# schemat.net
KiCad netlist of a schematic drawn in EAGLE
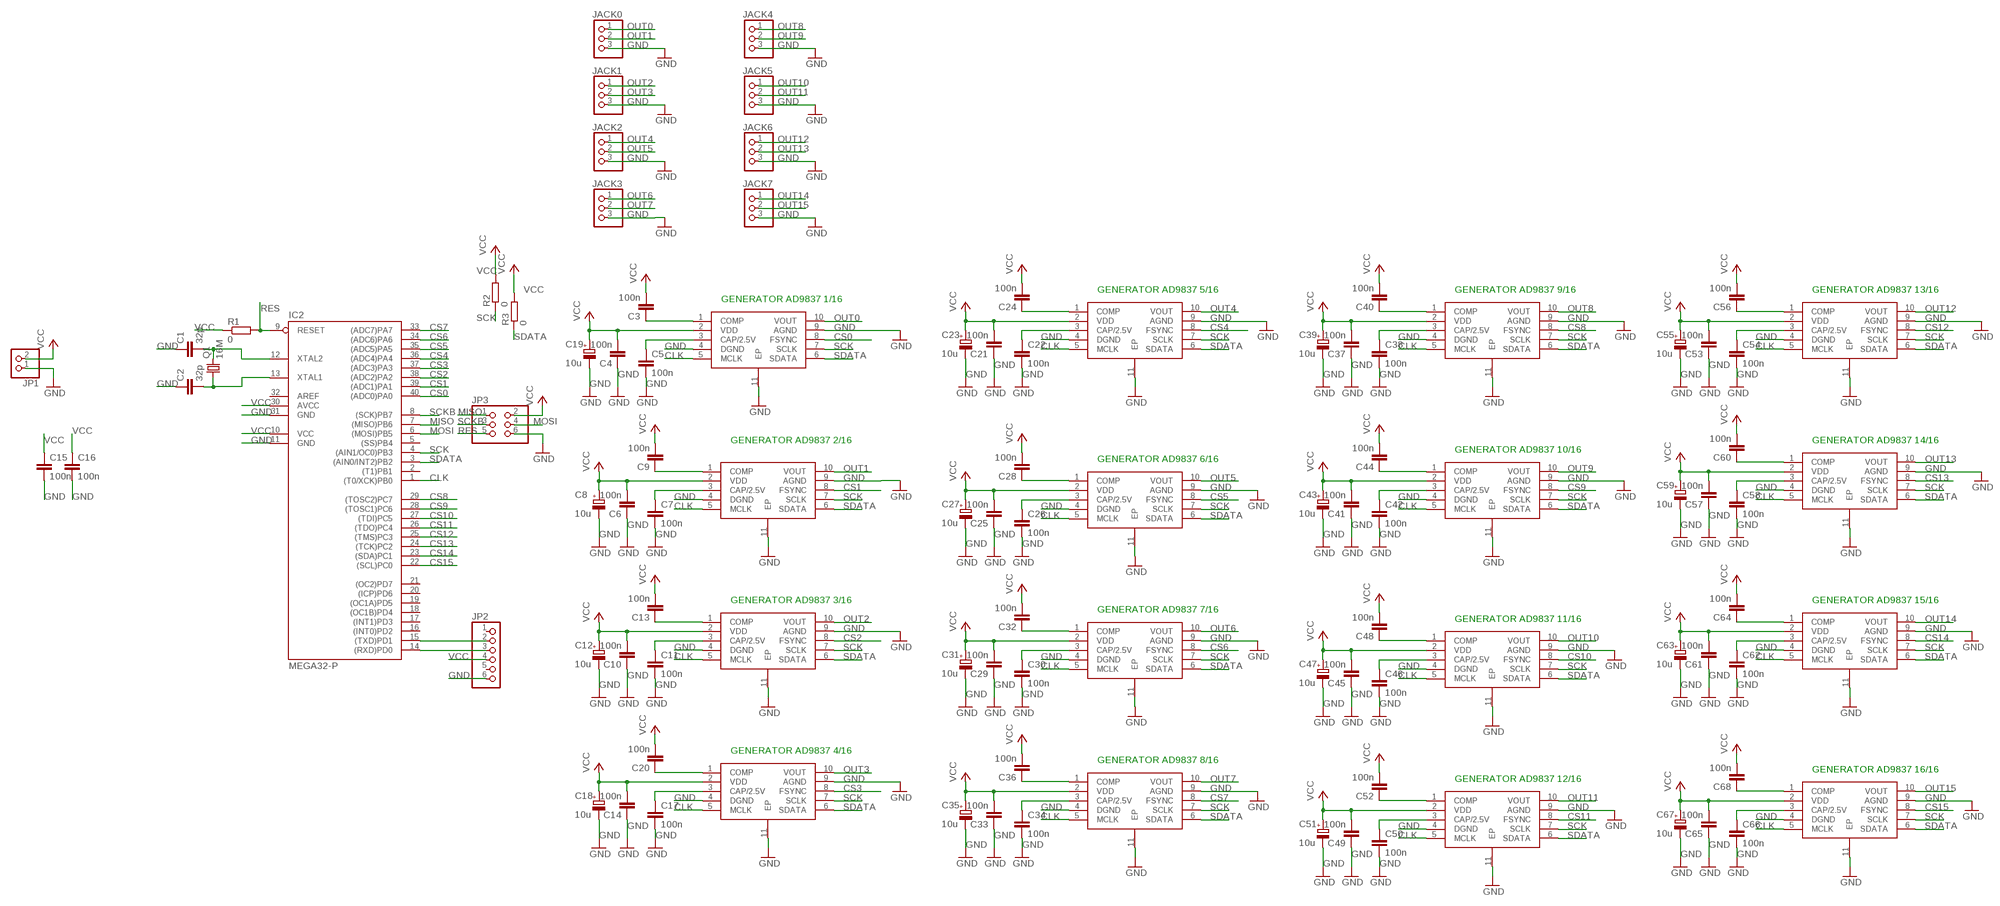
[diagram p0: schematic, sheet 1]

(export (version "E")
  (design (tool "Eeschema 10.0.6"))
  (components
    (comp (ref "C1")
      (value "32p")
      (footprint "eagle-import:C1206")
      (libsource (lib "eagle-import") (part "rcl_334_C-EUC1206"))
    )
    (comp (ref "C2")
      (value "32p")
      (footprint "eagle-import:C1206")
      (libsource (lib "eagle-import") (part "rcl_334_C-EUC1206"))
    )
    (comp (ref "C3")
      (value "100n")
      (footprint "eagle-import:C1206")
      (libsource (lib "eagle-import") (part "C-EUC1206"))
    )
    (comp (ref "C4")
      (value "100n")
      (footprint "eagle-import:C1206")
      (libsource (lib "eagle-import") (part "C-EUC1206"))
    )
    (comp (ref "C5")
      (value "100n")
      (footprint "eagle-import:C1206")
      (libsource (lib "eagle-import") (part "C-EUC1206"))
    )
    (comp (ref "C6")
      (value "100n")
      (footprint "eagle-import:C1206")
      (libsource (lib "eagle-import") (part "C-EUC1206"))
    )
    (comp (ref "C7")
      (value "100n")
      (footprint "eagle-import:C1206")
      (libsource (lib "eagle-import") (part "C-EUC1206"))
    )
    (comp (ref "C8")
      (value "10u")
      (footprint "eagle-import:SMC_B")
      (libsource (lib "eagle-import") (part "CPOL-EUSMCB"))
    )
    (comp (ref "C9")
      (value "100n")
      (footprint "eagle-import:C1206")
      (libsource (lib "eagle-import") (part "C-EUC1206"))
    )
    (comp (ref "C10")
      (value "100n")
      (footprint "eagle-import:C1206")
      (libsource (lib "eagle-import") (part "C-EUC1206"))
    )
    (comp (ref "C11")
      (value "100n")
      (footprint "eagle-import:C1206")
      (libsource (lib "eagle-import") (part "C-EUC1206"))
    )
    (comp (ref "C12")
      (value "10u")
      (footprint "eagle-import:SMC_B")
      (libsource (lib "eagle-import") (part "CPOL-EUSMCB"))
    )
    (comp (ref "C13")
      (value "100n")
      (footprint "eagle-import:C1206")
      (libsource (lib "eagle-import") (part "C-EUC1206"))
    )
    (comp (ref "C14")
      (value "100n")
      (footprint "eagle-import:C1206")
      (libsource (lib "eagle-import") (part "C-EUC1206"))
    )
    (comp (ref "C15")
      (value "100n")
      (footprint "eagle-import:C1206")
      (libsource (lib "eagle-import") (part "C-EUC1206"))
    )
    (comp (ref "C16")
      (value "100n")
      (footprint "eagle-import:C1206")
      (libsource (lib "eagle-import") (part "C-EUC1206"))
    )
    (comp (ref "C17")
      (value "100n")
      (footprint "eagle-import:C1206")
      (libsource (lib "eagle-import") (part "C-EUC1206"))
    )
    (comp (ref "C18")
      (value "10u")
      (footprint "eagle-import:SMC_B")
      (libsource (lib "eagle-import") (part "CPOL-EUSMCB"))
    )
    (comp (ref "C19")
      (value "10u")
      (footprint "eagle-import:SMC_B")
      (libsource (lib "eagle-import") (part "CPOL-EUSMCB"))
    )
    (comp (ref "C20")
      (value "100n")
      (footprint "eagle-import:C1206")
      (libsource (lib "eagle-import") (part "C-EUC1206"))
    )
    (comp (ref "C21")
      (value "100n")
      (footprint "eagle-import:C1206")
      (libsource (lib "eagle-import") (part "C-EUC1206"))
    )
    (comp (ref "C22")
      (value "100n")
      (footprint "eagle-import:C1206")
      (libsource (lib "eagle-import") (part "C-EUC1206"))
    )
    (comp (ref "C23")
      (value "10u")
      (footprint "eagle-import:SMC_B")
      (libsource (lib "eagle-import") (part "CPOL-EUSMCB"))
    )
    (comp (ref "C24")
      (value "100n")
      (footprint "eagle-import:C1206")
      (libsource (lib "eagle-import") (part "C-EUC1206"))
    )
    (comp (ref "C25")
      (value "100n")
      (footprint "eagle-import:C1206")
      (libsource (lib "eagle-import") (part "C-EUC1206"))
    )
    (comp (ref "C26")
      (value "100n")
      (footprint "eagle-import:C1206")
      (libsource (lib "eagle-import") (part "C-EUC1206"))
    )
    (comp (ref "C27")
      (value "10u")
      (footprint "eagle-import:SMC_B")
      (libsource (lib "eagle-import") (part "CPOL-EUSMCB"))
    )
    (comp (ref "C28")
      (value "100n")
      (footprint "eagle-import:C1206")
      (libsource (lib "eagle-import") (part "C-EUC1206"))
    )
    (comp (ref "C29")
      (value "100n")
      (footprint "eagle-import:C1206")
      (libsource (lib "eagle-import") (part "C-EUC1206"))
    )
    (comp (ref "C30")
      (value "100n")
      (footprint "eagle-import:C1206")
      (libsource (lib "eagle-import") (part "C-EUC1206"))
    )
    (comp (ref "C31")
      (value "10u")
      (footprint "eagle-import:SMC_B")
      (libsource (lib "eagle-import") (part "CPOL-EUSMCB"))
    )
    (comp (ref "C32")
      (value "100n")
      (footprint "eagle-import:C1206")
      (libsource (lib "eagle-import") (part "C-EUC1206"))
    )
    (comp (ref "C33")
      (value "100n")
      (footprint "eagle-import:C1206")
      (libsource (lib "eagle-import") (part "C-EUC1206"))
    )
    (comp (ref "C34")
      (value "100n")
      (footprint "eagle-import:C1206")
      (libsource (lib "eagle-import") (part "C-EUC1206"))
    )
    (comp (ref "C35")
      (value "10u")
      (footprint "eagle-import:SMC_B")
      (libsource (lib "eagle-import") (part "CPOL-EUSMCB"))
    )
    (comp (ref "C36")
      (value "100n")
      (footprint "eagle-import:C1206")
      (libsource (lib "eagle-import") (part "C-EUC1206"))
    )
    (comp (ref "C37")
      (value "100n")
      (footprint "eagle-import:C1206")
      (libsource (lib "eagle-import") (part "C-EUC1206"))
    )
    (comp (ref "C38")
      (value "100n")
      (footprint "eagle-import:C1206")
      (libsource (lib "eagle-import") (part "C-EUC1206"))
    )
    (comp (ref "C39")
      (value "10u")
      (footprint "eagle-import:SMC_B")
      (libsource (lib "eagle-import") (part "CPOL-EUSMCB"))
    )
    (comp (ref "C40")
      (value "100n")
      (footprint "eagle-import:C1206")
      (libsource (lib "eagle-import") (part "C-EUC1206"))
    )
    (comp (ref "C41")
      (value "100n")
      (footprint "eagle-import:C1206")
      (libsource (lib "eagle-import") (part "C-EUC1206"))
    )
    (comp (ref "C42")
      (value "100n")
      (footprint "eagle-import:C1206")
      (libsource (lib "eagle-import") (part "C-EUC1206"))
    )
    (comp (ref "C43")
      (value "10u")
      (footprint "eagle-import:SMC_B")
      (libsource (lib "eagle-import") (part "CPOL-EUSMCB"))
    )
    (comp (ref "C44")
      (value "100n")
      (footprint "eagle-import:C1206")
      (libsource (lib "eagle-import") (part "C-EUC1206"))
    )
    (comp (ref "C45")
      (value "100n")
      (footprint "eagle-import:C1206")
      (libsource (lib "eagle-import") (part "C-EUC1206"))
    )
    (comp (ref "C46")
      (value "100n")
      (footprint "eagle-import:C1206")
      (libsource (lib "eagle-import") (part "C-EUC1206"))
    )
    (comp (ref "C47")
      (value "10u")
      (footprint "eagle-import:SMC_B")
      (libsource (lib "eagle-import") (part "CPOL-EUSMCB"))
    )
    (comp (ref "C48")
      (value "100n")
      (footprint "eagle-import:C1206")
      (libsource (lib "eagle-import") (part "C-EUC1206"))
    )
    (comp (ref "C49")
      (value "100n")
      (footprint "eagle-import:C1206")
      (libsource (lib "eagle-import") (part "C-EUC1206"))
    )
    (comp (ref "C50")
      (value "100n")
      (footprint "eagle-import:C1206")
      (libsource (lib "eagle-import") (part "C-EUC1206"))
    )
    (comp (ref "C51")
      (value "10u")
      (footprint "eagle-import:SMC_B")
      (libsource (lib "eagle-import") (part "CPOL-EUSMCB"))
    )
    (comp (ref "C52")
      (value "100n")
      (footprint "eagle-import:C1206")
      (libsource (lib "eagle-import") (part "C-EUC1206"))
    )
    (comp (ref "C53")
      (value "100n")
      (footprint "eagle-import:C1206")
      (libsource (lib "eagle-import") (part "C-EUC1206"))
    )
    (comp (ref "C54")
      (value "100n")
      (footprint "eagle-import:C1206")
      (libsource (lib "eagle-import") (part "C-EUC1206"))
    )
    (comp (ref "C55")
      (value "10u")
      (footprint "eagle-import:SMC_B")
      (libsource (lib "eagle-import") (part "CPOL-EUSMCB"))
    )
    (comp (ref "C56")
      (value "100n")
      (footprint "eagle-import:C1206")
      (libsource (lib "eagle-import") (part "C-EUC1206"))
    )
    (comp (ref "C57")
      (value "100n")
      (footprint "eagle-import:C1206")
      (libsource (lib "eagle-import") (part "C-EUC1206"))
    )
    (comp (ref "C58")
      (value "100n")
      (footprint "eagle-import:C1206")
      (libsource (lib "eagle-import") (part "C-EUC1206"))
    )
    (comp (ref "C59")
      (value "10u")
      (footprint "eagle-import:SMC_B")
      (libsource (lib "eagle-import") (part "CPOL-EUSMCB"))
    )
    (comp (ref "C60")
      (value "100n")
      (footprint "eagle-import:C1206")
      (libsource (lib "eagle-import") (part "C-EUC1206"))
    )
    (comp (ref "C61")
      (value "100n")
      (footprint "eagle-import:C1206")
      (libsource (lib "eagle-import") (part "C-EUC1206"))
    )
    (comp (ref "C62")
      (value "100n")
      (footprint "eagle-import:C1206")
      (libsource (lib "eagle-import") (part "C-EUC1206"))
    )
    (comp (ref "C63")
      (value "10u")
      (footprint "eagle-import:SMC_B")
      (libsource (lib "eagle-import") (part "CPOL-EUSMCB"))
    )
    (comp (ref "C64")
      (value "100n")
      (footprint "eagle-import:C1206")
      (libsource (lib "eagle-import") (part "C-EUC1206"))
    )
    (comp (ref "C65")
      (value "100n")
      (footprint "eagle-import:C1206")
      (libsource (lib "eagle-import") (part "C-EUC1206"))
    )
    (comp (ref "C66")
      (value "100n")
      (footprint "eagle-import:C1206")
      (libsource (lib "eagle-import") (part "C-EUC1206"))
    )
    (comp (ref "C67")
      (value "10u")
      (footprint "eagle-import:SMC_B")
      (libsource (lib "eagle-import") (part "CPOL-EUSMCB"))
    )
    (comp (ref "C68")
      (value "100n")
      (footprint "eagle-import:C1206")
      (libsource (lib "eagle-import") (part "C-EUC1206"))
    )
    (comp (ref "GEN1")
      (value "AD9837")
      (footprint "eagle-import:SON50P300X300X80-11N")
      (fields (field (name "SPICEPREFIX") "X"))
      (libsource (lib "eagle-import") (part "AD9837"))
    )
    (comp (ref "GEN2")
      (value "AD9837")
      (footprint "eagle-import:SON50P300X300X80-11N")
      (libsource (lib "eagle-import") (part "AD9837"))
    )
    (comp (ref "GEN3")
      (value "AD9837")
      (footprint "eagle-import:SON50P300X300X80-11N")
      (libsource (lib "eagle-import") (part "AD9837"))
    )
    (comp (ref "GEN4")
      (value "AD9837")
      (footprint "eagle-import:SON50P300X300X80-11N")
      (libsource (lib "eagle-import") (part "AD9837"))
    )
    (comp (ref "GEN5")
      (value "AD9837")
      (footprint "eagle-import:SON50P300X300X80-11N")
      (libsource (lib "eagle-import") (part "AD9837"))
    )
    (comp (ref "GEN6")
      (value "AD9837")
      (footprint "eagle-import:SON50P300X300X80-11N")
      (libsource (lib "eagle-import") (part "AD9837"))
    )
    (comp (ref "GEN7")
      (value "AD9837")
      (footprint "eagle-import:SON50P300X300X80-11N")
      (libsource (lib "eagle-import") (part "AD9837"))
    )
    (comp (ref "GEN8")
      (value "AD9837")
      (footprint "eagle-import:SON50P300X300X80-11N")
      (libsource (lib "eagle-import") (part "AD9837"))
    )
    (comp (ref "GEN9")
      (value "AD9837")
      (footprint "eagle-import:SON50P300X300X80-11N")
      (libsource (lib "eagle-import") (part "AD9837"))
    )
    (comp (ref "GEN10")
      (value "AD9837")
      (footprint "eagle-import:SON50P300X300X80-11N")
      (libsource (lib "eagle-import") (part "AD9837"))
    )
    (comp (ref "GEN11")
      (value "AD9837")
      (footprint "eagle-import:SON50P300X300X80-11N")
      (libsource (lib "eagle-import") (part "AD9837"))
    )
    (comp (ref "GEN12")
      (value "AD9837")
      (footprint "eagle-import:SON50P300X300X80-11N")
      (libsource (lib "eagle-import") (part "AD9837"))
    )
    (comp (ref "GEN13")
      (value "AD9837")
      (footprint "eagle-import:SON50P300X300X80-11N")
      (libsource (lib "eagle-import") (part "AD9837"))
    )
    (comp (ref "GEN14")
      (value "AD9837")
      (footprint "eagle-import:SON50P300X300X80-11N")
      (libsource (lib "eagle-import") (part "AD9837"))
    )
    (comp (ref "GEN15")
      (value "AD9837")
      (footprint "eagle-import:SON50P300X300X80-11N")
      (libsource (lib "eagle-import") (part "AD9837"))
    )
    (comp (ref "GEN16")
      (value "AD9837")
      (footprint "eagle-import:SON50P300X300X80-11N")
      (libsource (lib "eagle-import") (part "AD9837"))
    )
    (comp (ref "IC2")
      (value "MEGA32-P")
      (footprint "eagle-import:DIL40")
      (fields (field (name "MPN") "ATMEGA32-16PU"))
      (libsource (lib "eagle-import") (part "MEGA32-P"))
    )
    (comp (ref "JACK0")
      (value "PINHD-1X3")
      (footprint "eagle-import:1X03")
      (libsource (lib "eagle-import") (part "PINHD-1X3"))
    )
    (comp (ref "JACK1")
      (value "PINHD-1X3")
      (footprint "eagle-import:1X03")
      (libsource (lib "eagle-import") (part "PINHD-1X3"))
    )
    (comp (ref "JACK2")
      (value "PINHD-1X3")
      (footprint "eagle-import:1X03")
      (libsource (lib "eagle-import") (part "PINHD-1X3"))
    )
    (comp (ref "JACK3")
      (value "PINHD-1X3")
      (footprint "eagle-import:1X03")
      (libsource (lib "eagle-import") (part "PINHD-1X3"))
    )
    (comp (ref "JACK4")
      (value "PINHD-1X3")
      (footprint "eagle-import:1X03")
      (libsource (lib "eagle-import") (part "PINHD-1X3"))
    )
    (comp (ref "JACK5")
      (value "PINHD-1X3")
      (footprint "eagle-import:1X03")
      (libsource (lib "eagle-import") (part "PINHD-1X3"))
    )
    (comp (ref "JACK6")
      (value "PINHD-1X3")
      (footprint "eagle-import:1X03")
      (libsource (lib "eagle-import") (part "PINHD-1X3"))
    )
    (comp (ref "JACK7")
      (value "PINHD-1X3")
      (footprint "eagle-import:1X03")
      (libsource (lib "eagle-import") (part "PINHD-1X3"))
    )
    (comp (ref "JP1")
      (value "PINHD-1X2")
      (footprint "eagle-import:1X02")
      (libsource (lib "eagle-import") (part "PINHD-1X2"))
    )
    (comp (ref "JP2")
      (value "PINHD-1X6")
      (footprint "eagle-import:1X06")
      (libsource (lib "eagle-import") (part "PINHD-1X6"))
    )
    (comp (ref "JP3")
      (value "PINHD-2X3")
      (footprint "eagle-import:2X03")
      (libsource (lib "eagle-import") (part "PINHD-2X3"))
    )
    (comp (ref "Q1")
      (value "16M")
      (footprint "eagle-import:HC49_S")
      (libsource (lib "eagle-import") (part "CRYSTALHC49S"))
    )
    (comp (ref "R1")
      (value "0")
      (footprint "eagle-import:R1206")
      (libsource (lib "eagle-import") (part "rcl_334_R-EU_R1206"))
    )
    (comp (ref "R2")
      (value "0")
      (footprint "eagle-import:M1206")
      (libsource (lib "eagle-import") (part "R-EU_M1206"))
    )
    (comp (ref "R3")
      (value "0")
      (footprint "eagle-import:M1206")
      (libsource (lib "eagle-import") (part "R-EU_M1206"))
    )
  )
  (nets
    (net (code "1") (name "/CLK") (class "Default")
      (node (ref "GEN1") (pin "5") (pinfunction "MCLK_5") (pintype "bidirectional"))
      (node (ref "GEN10") (pin "5") (pinfunction "MCLK_5") (pintype "bidirectional"))
      (node (ref "GEN11") (pin "5") (pinfunction "MCLK_5") (pintype "bidirectional"))
      (node (ref "GEN12") (pin "5") (pinfunction "MCLK_5") (pintype "bidirectional"))
      (node (ref "GEN13") (pin "5") (pinfunction "MCLK_5") (pintype "bidirectional"))
      (node (ref "GEN14") (pin "5") (pinfunction "MCLK_5") (pintype "bidirectional"))
      (node (ref "GEN15") (pin "5") (pinfunction "MCLK_5") (pintype "bidirectional"))
      (node (ref "GEN16") (pin "5") (pinfunction "MCLK_5") (pintype "bidirectional"))
      (node (ref "GEN2") (pin "5") (pinfunction "MCLK_5") (pintype "bidirectional"))
      (node (ref "GEN3") (pin "5") (pinfunction "MCLK_5") (pintype "bidirectional"))
      (node (ref "GEN4") (pin "5") (pinfunction "MCLK_5") (pintype "bidirectional"))
      (node (ref "GEN5") (pin "5") (pinfunction "MCLK_5") (pintype "bidirectional"))
      (node (ref "GEN6") (pin "5") (pinfunction "MCLK_5") (pintype "bidirectional"))
      (node (ref "GEN7") (pin "5") (pinfunction "MCLK_5") (pintype "bidirectional"))
      (node (ref "GEN8") (pin "5") (pinfunction "MCLK_5") (pintype "bidirectional"))
      (node (ref "GEN9") (pin "5") (pinfunction "MCLK_5") (pintype "bidirectional"))
      (node (ref "IC2") (pin "1") (pinfunction "(T0/XCK)PB0_1") (pintype "bidirectional"))
    )
    (net (code "2") (name "/CS0") (class "Default")
      (node (ref "GEN1") (pin "8") (pinfunction "FSYNC_8") (pintype "bidirectional"))
      (node (ref "IC2") (pin "40") (pinfunction "(ADC0)PA0_40") (pintype "bidirectional"))
    )
    (net (code "3") (name "/CS1") (class "Default")
      (node (ref "GEN2") (pin "8") (pinfunction "FSYNC_8") (pintype "bidirectional"))
      (node (ref "IC2") (pin "39") (pinfunction "(ADC1)PA1_39") (pintype "bidirectional"))
    )
    (net (code "4") (name "/CS2") (class "Default")
      (node (ref "GEN3") (pin "8") (pinfunction "FSYNC_8") (pintype "bidirectional"))
      (node (ref "IC2") (pin "38") (pinfunction "(ADC2)PA2_38") (pintype "bidirectional"))
    )
    (net (code "5") (name "/CS3") (class "Default")
      (node (ref "GEN4") (pin "8") (pinfunction "FSYNC_8") (pintype "bidirectional"))
      (node (ref "IC2") (pin "37") (pinfunction "(ADC3)PA3_37") (pintype "bidirectional"))
    )
    (net (code "6") (name "/CS4") (class "Default")
      (node (ref "GEN5") (pin "8") (pinfunction "FSYNC_8") (pintype "bidirectional"))
      (node (ref "IC2") (pin "36") (pinfunction "(ADC4)PA4_36") (pintype "bidirectional"))
    )
    (net (code "7") (name "/CS5") (class "Default")
      (node (ref "GEN6") (pin "8") (pinfunction "FSYNC_8") (pintype "bidirectional"))
      (node (ref "IC2") (pin "35") (pinfunction "(ADC5)PA5_35") (pintype "bidirectional"))
    )
    (net (code "8") (name "/CS6") (class "Default")
      (node (ref "GEN7") (pin "8") (pinfunction "FSYNC_8") (pintype "bidirectional"))
      (node (ref "IC2") (pin "34") (pinfunction "(ADC6)PA6_34") (pintype "bidirectional"))
    )
    (net (code "9") (name "/CS7") (class "Default")
      (node (ref "GEN8") (pin "8") (pinfunction "FSYNC_8") (pintype "bidirectional"))
      (node (ref "IC2") (pin "33") (pinfunction "(ADC7)PA7_33") (pintype "bidirectional"))
    )
    (net (code "10") (name "/CS8") (class "Default")
      (node (ref "GEN9") (pin "8") (pinfunction "FSYNC_8") (pintype "bidirectional"))
      (node (ref "IC2") (pin "29") (pinfunction "(TOSC2)PC7_29") (pintype "bidirectional"))
    )
    (net (code "11") (name "/CS9") (class "Default")
      (node (ref "GEN10") (pin "8") (pinfunction "FSYNC_8") (pintype "bidirectional"))
      (node (ref "IC2") (pin "28") (pinfunction "(TOSC1)PC6_28") (pintype "bidirectional"))
    )
    (net (code "12") (name "/CS10") (class "Default")
      (node (ref "GEN11") (pin "8") (pinfunction "FSYNC_8") (pintype "bidirectional"))
      (node (ref "IC2") (pin "27") (pinfunction "(TDI)PC5_27") (pintype "bidirectional"))
    )
    (net (code "13") (name "/CS11") (class "Default")
      (node (ref "GEN12") (pin "8") (pinfunction "FSYNC_8") (pintype "bidirectional"))
      (node (ref "IC2") (pin "26") (pinfunction "(TDO)PC4_26") (pintype "bidirectional"))
    )
    (net (code "14") (name "/CS12") (class "Default")
      (node (ref "GEN13") (pin "8") (pinfunction "FSYNC_8") (pintype "bidirectional"))
      (node (ref "IC2") (pin "25") (pinfunction "(TMS)PC3_25") (pintype "bidirectional"))
    )
    (net (code "15") (name "/CS13") (class "Default")
      (node (ref "GEN14") (pin "8") (pinfunction "FSYNC_8") (pintype "bidirectional"))
      (node (ref "IC2") (pin "24") (pinfunction "(TCK)PC2_24") (pintype "bidirectional"))
    )
    (net (code "16") (name "/CS14") (class "Default")
      (node (ref "GEN15") (pin "8") (pinfunction "FSYNC_8") (pintype "bidirectional"))
      (node (ref "IC2") (pin "23") (pinfunction "(SDA)PC1_23") (pintype "bidirectional"))
    )
    (net (code "17") (name "/CS15") (class "Default")
      (node (ref "GEN16") (pin "8") (pinfunction "FSYNC_8") (pintype "bidirectional"))
      (node (ref "IC2") (pin "22") (pinfunction "(SCL)PC0_22") (pintype "bidirectional"))
    )
    (net (code "18") (name "/MISO") (class "Default")
      (node (ref "IC2") (pin "7") (pinfunction "(MISO)PB6_7") (pintype "bidirectional"))
      (node (ref "JP3") (pin "1") (pinfunction "1_1") (pintype "passive"))
    )
    (net (code "19") (name "/MOSI") (class "Default")
      (node (ref "IC2") (pin "6") (pinfunction "(MOSI)PB5_6") (pintype "bidirectional"))
      (node (ref "JP3") (pin "4") (pinfunction "4_4") (pintype "passive"))
    )
    (net (code "20") (name "/OUT0") (class "Default")
      (node (ref "GEN1") (pin "10") (pinfunction "VOUT_10") (pintype "bidirectional"))
      (node (ref "JACK0") (pin "1") (pinfunction "1_1") (pintype "passive"))
    )
    (net (code "21") (name "/OUT1") (class "Default")
      (node (ref "GEN2") (pin "10") (pinfunction "VOUT_10") (pintype "bidirectional"))
      (node (ref "JACK0") (pin "2") (pinfunction "2_2") (pintype "passive"))
    )
    (net (code "22") (name "/OUT2") (class "Default")
      (node (ref "GEN3") (pin "10") (pinfunction "VOUT_10") (pintype "bidirectional"))
      (node (ref "JACK1") (pin "1") (pinfunction "1_1") (pintype "passive"))
    )
    (net (code "23") (name "/OUT3") (class "Default")
      (node (ref "GEN4") (pin "10") (pinfunction "VOUT_10") (pintype "bidirectional"))
      (node (ref "JACK1") (pin "2") (pinfunction "2_2") (pintype "passive"))
    )
    (net (code "24") (name "/OUT4") (class "Default")
      (node (ref "GEN5") (pin "10") (pinfunction "VOUT_10") (pintype "bidirectional"))
      (node (ref "JACK2") (pin "1") (pinfunction "1_1") (pintype "passive"))
    )
    (net (code "25") (name "/OUT5") (class "Default")
      (node (ref "GEN6") (pin "10") (pinfunction "VOUT_10") (pintype "bidirectional"))
      (node (ref "JACK2") (pin "2") (pinfunction "2_2") (pintype "passive"))
    )
    (net (code "26") (name "/OUT6") (class "Default")
      (node (ref "GEN7") (pin "10") (pinfunction "VOUT_10") (pintype "bidirectional"))
      (node (ref "JACK3") (pin "1") (pinfunction "1_1") (pintype "passive"))
    )
    (net (code "27") (name "/OUT7") (class "Default")
      (node (ref "GEN8") (pin "10") (pinfunction "VOUT_10") (pintype "bidirectional"))
      (node (ref "JACK3") (pin "2") (pinfunction "2_2") (pintype "passive"))
    )
    (net (code "28") (name "/OUT8") (class "Default")
      (node (ref "GEN9") (pin "10") (pinfunction "VOUT_10") (pintype "bidirectional"))
      (node (ref "JACK4") (pin "1") (pinfunction "1_1") (pintype "passive"))
    )
    (net (code "29") (name "/OUT9") (class "Default")
      (node (ref "GEN10") (pin "10") (pinfunction "VOUT_10") (pintype "bidirectional"))
      (node (ref "JACK4") (pin "2") (pinfunction "2_2") (pintype "passive"))
    )
    (net (code "30") (name "/OUT10") (class "Default")
      (node (ref "GEN11") (pin "10") (pinfunction "VOUT_10") (pintype "bidirectional"))
      (node (ref "JACK5") (pin "1") (pinfunction "1_1") (pintype "passive"))
    )
    (net (code "31") (name "/OUT11") (class "Default")
      (node (ref "GEN12") (pin "10") (pinfunction "VOUT_10") (pintype "bidirectional"))
      (node (ref "JACK5") (pin "2") (pinfunction "2_2") (pintype "passive"))
    )
    (net (code "32") (name "/OUT12") (class "Default")
      (node (ref "GEN13") (pin "10") (pinfunction "VOUT_10") (pintype "bidirectional"))
      (node (ref "JACK6") (pin "1") (pinfunction "1_1") (pintype "passive"))
    )
    (net (code "33") (name "/OUT13") (class "Default")
      (node (ref "GEN14") (pin "10") (pinfunction "VOUT_10") (pintype "bidirectional"))
      (node (ref "JACK6") (pin "2") (pinfunction "2_2") (pintype "passive"))
    )
    (net (code "34") (name "/OUT14") (class "Default")
      (node (ref "GEN15") (pin "10") (pinfunction "VOUT_10") (pintype "bidirectional"))
      (node (ref "JACK7") (pin "1") (pinfunction "1_1") (pintype "passive"))
    )
    (net (code "35") (name "/OUT15") (class "Default")
      (node (ref "GEN16") (pin "10") (pinfunction "VOUT_10") (pintype "bidirectional"))
      (node (ref "JACK7") (pin "2") (pinfunction "2_2") (pintype "passive"))
    )
    (net (code "36") (name "/RES") (class "Default")
      (node (ref "IC2") (pin "9") (pinfunction "RESET_9") (pintype "input"))
      (node (ref "JP3") (pin "5") (pinfunction "5_5") (pintype "passive"))
      (node (ref "R1") (pin "2") (pinfunction "2_2") (pintype "passive"))
    )
    (net (code "37") (name "/SCK") (class "Default")
      (node (ref "GEN1") (pin "7") (pinfunction "SCLK_7") (pintype "bidirectional"))
      (node (ref "GEN10") (pin "7") (pinfunction "SCLK_7") (pintype "bidirectional"))
      (node (ref "GEN11") (pin "7") (pinfunction "SCLK_7") (pintype "bidirectional"))
      (node (ref "GEN12") (pin "7") (pinfunction "SCLK_7") (pintype "bidirectional"))
      (node (ref "GEN13") (pin "7") (pinfunction "SCLK_7") (pintype "bidirectional"))
      (node (ref "GEN14") (pin "7") (pinfunction "SCLK_7") (pintype "bidirectional"))
      (node (ref "GEN15") (pin "7") (pinfunction "SCLK_7") (pintype "bidirectional"))
      (node (ref "GEN16") (pin "7") (pinfunction "SCLK_7") (pintype "bidirectional"))
      (node (ref "GEN2") (pin "7") (pinfunction "SCLK_7") (pintype "bidirectional"))
      (node (ref "GEN3") (pin "7") (pinfunction "SCLK_7") (pintype "bidirectional"))
      (node (ref "GEN4") (pin "7") (pinfunction "SCLK_7") (pintype "bidirectional"))
      (node (ref "GEN5") (pin "7") (pinfunction "SCLK_7") (pintype "bidirectional"))
      (node (ref "GEN6") (pin "7") (pinfunction "SCLK_7") (pintype "bidirectional"))
      (node (ref "GEN7") (pin "7") (pinfunction "SCLK_7") (pintype "bidirectional"))
      (node (ref "GEN8") (pin "7") (pinfunction "SCLK_7") (pintype "bidirectional"))
      (node (ref "GEN9") (pin "7") (pinfunction "SCLK_7") (pintype "bidirectional"))
      (node (ref "IC2") (pin "4") (pinfunction "(AIN1/OC0)PB3_4") (pintype "bidirectional"))
      (node (ref "R2") (pin "1") (pinfunction "1_1") (pintype "passive"))
    )
    (net (code "38") (name "/SCKB") (class "Default")
      (node (ref "IC2") (pin "8") (pinfunction "(SCK)PB7_8") (pintype "bidirectional"))
      (node (ref "JP3") (pin "3") (pinfunction "3_3") (pintype "passive"))
    )
    (net (code "39") (name "/SDATA") (class "Default")
      (node (ref "GEN1") (pin "6") (pinfunction "SDATA_6") (pintype "bidirectional"))
      (node (ref "GEN10") (pin "6") (pinfunction "SDATA_6") (pintype "bidirectional"))
      (node (ref "GEN11") (pin "6") (pinfunction "SDATA_6") (pintype "bidirectional"))
      (node (ref "GEN12") (pin "6") (pinfunction "SDATA_6") (pintype "bidirectional"))
      (node (ref "GEN13") (pin "6") (pinfunction "SDATA_6") (pintype "bidirectional"))
      (node (ref "GEN14") (pin "6") (pinfunction "SDATA_6") (pintype "bidirectional"))
      (node (ref "GEN15") (pin "6") (pinfunction "SDATA_6") (pintype "bidirectional"))
      (node (ref "GEN16") (pin "6") (pinfunction "SDATA_6") (pintype "bidirectional"))
      (node (ref "GEN2") (pin "6") (pinfunction "SDATA_6") (pintype "bidirectional"))
      (node (ref "GEN3") (pin "6") (pinfunction "SDATA_6") (pintype "bidirectional"))
      (node (ref "GEN4") (pin "6") (pinfunction "SDATA_6") (pintype "bidirectional"))
      (node (ref "GEN5") (pin "6") (pinfunction "SDATA_6") (pintype "bidirectional"))
      (node (ref "GEN6") (pin "6") (pinfunction "SDATA_6") (pintype "bidirectional"))
      (node (ref "GEN7") (pin "6") (pinfunction "SDATA_6") (pintype "bidirectional"))
      (node (ref "GEN8") (pin "6") (pinfunction "SDATA_6") (pintype "bidirectional"))
      (node (ref "GEN9") (pin "6") (pinfunction "SDATA_6") (pintype "bidirectional"))
      (node (ref "IC2") (pin "3") (pinfunction "(AIN0/INT2)PB2_3") (pintype "bidirectional"))
      (node (ref "R3") (pin "1") (pinfunction "1_1") (pintype "passive"))
    )
    (net (code "40") (name "GND") (class "Default")
      (node (ref "C1") (pin "1") (pinfunction "1_1") (pintype "passive"))
      (node (ref "C10") (pin "1") (pinfunction "1_1") (pintype "passive"))
      (node (ref "C11") (pin "2") (pinfunction "2_2") (pintype "passive"))
      (node (ref "C12") (pin "-") (pinfunction "-_-") (pintype "passive"))
      (node (ref "C14") (pin "1") (pinfunction "1_1") (pintype "passive"))
      (node (ref "C15") (pin "2") (pinfunction "2_2") (pintype "passive"))
      (node (ref "C16") (pin "2") (pinfunction "2_2") (pintype "passive"))
      (node (ref "C17") (pin "2") (pinfunction "2_2") (pintype "passive"))
      (node (ref "C18") (pin "-") (pinfunction "-_-") (pintype "passive"))
      (node (ref "C19") (pin "-") (pinfunction "-_-") (pintype "passive"))
      (node (ref "C2") (pin "1") (pinfunction "1_1") (pintype "passive"))
      (node (ref "C21") (pin "1") (pinfunction "1_1") (pintype "passive"))
      (node (ref "C22") (pin "2") (pinfunction "2_2") (pintype "passive"))
      (node (ref "C23") (pin "-") (pinfunction "-_-") (pintype "passive"))
      (node (ref "C25") (pin "1") (pinfunction "1_1") (pintype "passive"))
      (node (ref "C26") (pin "2") (pinfunction "2_2") (pintype "passive"))
      (node (ref "C27") (pin "-") (pinfunction "-_-") (pintype "passive"))
      (node (ref "C29") (pin "1") (pinfunction "1_1") (pintype "passive"))
      (node (ref "C30") (pin "2") (pinfunction "2_2") (pintype "passive"))
      (node (ref "C31") (pin "-") (pinfunction "-_-") (pintype "passive"))
      (node (ref "C33") (pin "1") (pinfunction "1_1") (pintype "passive"))
      (node (ref "C34") (pin "2") (pinfunction "2_2") (pintype "passive"))
      (node (ref "C35") (pin "-") (pinfunction "-_-") (pintype "passive"))
      (node (ref "C37") (pin "1") (pinfunction "1_1") (pintype "passive"))
      (node (ref "C38") (pin "2") (pinfunction "2_2") (pintype "passive"))
      (node (ref "C39") (pin "-") (pinfunction "-_-") (pintype "passive"))
      (node (ref "C4") (pin "1") (pinfunction "1_1") (pintype "passive"))
      (node (ref "C41") (pin "1") (pinfunction "1_1") (pintype "passive"))
      (node (ref "C42") (pin "2") (pinfunction "2_2") (pintype "passive"))
      (node (ref "C43") (pin "-") (pinfunction "-_-") (pintype "passive"))
      (node (ref "C45") (pin "1") (pinfunction "1_1") (pintype "passive"))
      (node (ref "C46") (pin "2") (pinfunction "2_2") (pintype "passive"))
      (node (ref "C47") (pin "-") (pinfunction "-_-") (pintype "passive"))
      (node (ref "C49") (pin "1") (pinfunction "1_1") (pintype "passive"))
      (node (ref "C5") (pin "2") (pinfunction "2_2") (pintype "passive"))
      (node (ref "C50") (pin "2") (pinfunction "2_2") (pintype "passive"))
      (node (ref "C51") (pin "-") (pinfunction "-_-") (pintype "passive"))
      (node (ref "C53") (pin "1") (pinfunction "1_1") (pintype "passive"))
      (node (ref "C54") (pin "2") (pinfunction "2_2") (pintype "passive"))
      (node (ref "C55") (pin "-") (pinfunction "-_-") (pintype "passive"))
      (node (ref "C57") (pin "1") (pinfunction "1_1") (pintype "passive"))
      (node (ref "C58") (pin "2") (pinfunction "2_2") (pintype "passive"))
      (node (ref "C59") (pin "-") (pinfunction "-_-") (pintype "passive"))
      (node (ref "C6") (pin "1") (pinfunction "1_1") (pintype "passive"))
      (node (ref "C61") (pin "1") (pinfunction "1_1") (pintype "passive"))
      (node (ref "C62") (pin "2") (pinfunction "2_2") (pintype "passive"))
      (node (ref "C63") (pin "-") (pinfunction "-_-") (pintype "passive"))
      (node (ref "C65") (pin "1") (pinfunction "1_1") (pintype "passive"))
      (node (ref "C66") (pin "2") (pinfunction "2_2") (pintype "passive"))
      (node (ref "C67") (pin "-") (pinfunction "-_-") (pintype "passive"))
      (node (ref "C7") (pin "2") (pinfunction "2_2") (pintype "passive"))
      (node (ref "C8") (pin "-") (pinfunction "-_-") (pintype "passive"))
      (node (ref "GEN1") (pin "11") (pinfunction "EP_11") (pintype "bidirectional"))
      (node (ref "GEN1") (pin "4") (pinfunction "DGND_4") (pintype "bidirectional"))
      (node (ref "GEN1") (pin "9") (pinfunction "AGND_9") (pintype "bidirectional"))
      (node (ref "GEN10") (pin "11") (pinfunction "EP_11") (pintype "bidirectional"))
      (node (ref "GEN10") (pin "4") (pinfunction "DGND_4") (pintype "bidirectional"))
      (node (ref "GEN10") (pin "9") (pinfunction "AGND_9") (pintype "bidirectional"))
      (node (ref "GEN11") (pin "11") (pinfunction "EP_11") (pintype "bidirectional"))
      (node (ref "GEN11") (pin "4") (pinfunction "DGND_4") (pintype "bidirectional"))
      (node (ref "GEN11") (pin "9") (pinfunction "AGND_9") (pintype "bidirectional"))
      (node (ref "GEN12") (pin "11") (pinfunction "EP_11") (pintype "bidirectional"))
      (node (ref "GEN12") (pin "4") (pinfunction "DGND_4") (pintype "bidirectional"))
      (node (ref "GEN12") (pin "9") (pinfunction "AGND_9") (pintype "bidirectional"))
      (node (ref "GEN13") (pin "11") (pinfunction "EP_11") (pintype "bidirectional"))
      (node (ref "GEN13") (pin "4") (pinfunction "DGND_4") (pintype "bidirectional"))
      (node (ref "GEN13") (pin "9") (pinfunction "AGND_9") (pintype "bidirectional"))
      (node (ref "GEN14") (pin "11") (pinfunction "EP_11") (pintype "bidirectional"))
      (node (ref "GEN14") (pin "4") (pinfunction "DGND_4") (pintype "bidirectional"))
      (node (ref "GEN14") (pin "9") (pinfunction "AGND_9") (pintype "bidirectional"))
      (node (ref "GEN15") (pin "11") (pinfunction "EP_11") (pintype "bidirectional"))
      (node (ref "GEN15") (pin "4") (pinfunction "DGND_4") (pintype "bidirectional"))
      (node (ref "GEN15") (pin "9") (pinfunction "AGND_9") (pintype "bidirectional"))
      (node (ref "GEN16") (pin "11") (pinfunction "EP_11") (pintype "bidirectional"))
      (node (ref "GEN16") (pin "4") (pinfunction "DGND_4") (pintype "bidirectional"))
      (node (ref "GEN16") (pin "9") (pinfunction "AGND_9") (pintype "bidirectional"))
      (node (ref "GEN2") (pin "11") (pinfunction "EP_11") (pintype "bidirectional"))
      (node (ref "GEN2") (pin "4") (pinfunction "DGND_4") (pintype "bidirectional"))
      (node (ref "GEN2") (pin "9") (pinfunction "AGND_9") (pintype "bidirectional"))
      (node (ref "GEN3") (pin "11") (pinfunction "EP_11") (pintype "bidirectional"))
      (node (ref "GEN3") (pin "4") (pinfunction "DGND_4") (pintype "bidirectional"))
      (node (ref "GEN3") (pin "9") (pinfunction "AGND_9") (pintype "bidirectional"))
      (node (ref "GEN4") (pin "11") (pinfunction "EP_11") (pintype "bidirectional"))
      (node (ref "GEN4") (pin "4") (pinfunction "DGND_4") (pintype "bidirectional"))
      (node (ref "GEN4") (pin "9") (pinfunction "AGND_9") (pintype "bidirectional"))
      (node (ref "GEN5") (pin "11") (pinfunction "EP_11") (pintype "bidirectional"))
      (node (ref "GEN5") (pin "4") (pinfunction "DGND_4") (pintype "bidirectional"))
      (node (ref "GEN5") (pin "9") (pinfunction "AGND_9") (pintype "bidirectional"))
      (node (ref "GEN6") (pin "11") (pinfunction "EP_11") (pintype "bidirectional"))
      (node (ref "GEN6") (pin "4") (pinfunction "DGND_4") (pintype "bidirectional"))
      (node (ref "GEN6") (pin "9") (pinfunction "AGND_9") (pintype "bidirectional"))
      (node (ref "GEN7") (pin "11") (pinfunction "EP_11") (pintype "bidirectional"))
      (node (ref "GEN7") (pin "4") (pinfunction "DGND_4") (pintype "bidirectional"))
      (node (ref "GEN7") (pin "9") (pinfunction "AGND_9") (pintype "bidirectional"))
      (node (ref "GEN8") (pin "11") (pinfunction "EP_11") (pintype "bidirectional"))
      (node (ref "GEN8") (pin "4") (pinfunction "DGND_4") (pintype "bidirectional"))
      (node (ref "GEN8") (pin "9") (pinfunction "AGND_9") (pintype "bidirectional"))
      (node (ref "GEN9") (pin "11") (pinfunction "EP_11") (pintype "bidirectional"))
      (node (ref "GEN9") (pin "4") (pinfunction "DGND_4") (pintype "bidirectional"))
      (node (ref "GEN9") (pin "9") (pinfunction "AGND_9") (pintype "bidirectional"))
      (node (ref "IC2") (pin "11") (pinfunction "GND_11") (pintype "power_in"))
      (node (ref "IC2") (pin "31") (pinfunction "GND_31") (pintype "power_in"))
      (node (ref "JACK0") (pin "3") (pinfunction "3_3") (pintype "passive"))
      (node (ref "JACK1") (pin "3") (pinfunction "3_3") (pintype "passive"))
      (node (ref "JACK2") (pin "3") (pinfunction "3_3") (pintype "passive"))
      (node (ref "JACK3") (pin "3") (pinfunction "3_3") (pintype "passive"))
      (node (ref "JACK4") (pin "3") (pinfunction "3_3") (pintype "passive"))
      (node (ref "JACK5") (pin "3") (pinfunction "3_3") (pintype "passive"))
      (node (ref "JACK6") (pin "3") (pinfunction "3_3") (pintype "passive"))
      (node (ref "JACK7") (pin "3") (pinfunction "3_3") (pintype "passive"))
      (node (ref "JP1") (pin "1") (pinfunction "1_1") (pintype "passive"))
      (node (ref "JP2") (pin "6") (pinfunction "6_6") (pintype "passive"))
      (node (ref "JP3") (pin "6") (pinfunction "6_6") (pintype "passive"))
    )
    (net (code "41") (name "Net-(GEN1-CAP{slash}2.5V)") (class "Default")
      (node (ref "C5") (pin "1") (pinfunction "1_1") (pintype "passive"))
      (node (ref "GEN1") (pin "3") (pinfunction "CAP/2.5V_3") (pintype "bidirectional"))
    )
    (net (code "42") (name "Net-(GEN1-COMP)") (class "Default")
      (node (ref "C3") (pin "1") (pinfunction "1_1") (pintype "passive"))
      (node (ref "GEN1") (pin "1") (pinfunction "COMP_1") (pintype "bidirectional"))
    )
    (net (code "43") (name "Net-(GEN2-CAP{slash}2.5V)") (class "Default")
      (node (ref "C7") (pin "1") (pinfunction "1_1") (pintype "passive"))
      (node (ref "GEN2") (pin "3") (pinfunction "CAP/2.5V_3") (pintype "bidirectional"))
    )
    (net (code "44") (name "Net-(GEN2-COMP)") (class "Default")
      (node (ref "C9") (pin "1") (pinfunction "1_1") (pintype "passive"))
      (node (ref "GEN2") (pin "1") (pinfunction "COMP_1") (pintype "bidirectional"))
    )
    (net (code "45") (name "Net-(GEN3-CAP{slash}2.5V)") (class "Default")
      (node (ref "C11") (pin "1") (pinfunction "1_1") (pintype "passive"))
      (node (ref "GEN3") (pin "3") (pinfunction "CAP/2.5V_3") (pintype "bidirectional"))
    )
    (net (code "46") (name "Net-(GEN3-COMP)") (class "Default")
      (node (ref "C13") (pin "1") (pinfunction "1_1") (pintype "passive"))
      (node (ref "GEN3") (pin "1") (pinfunction "COMP_1") (pintype "bidirectional"))
    )
    (net (code "47") (name "Net-(GEN4-CAP{slash}2.5V)") (class "Default")
      (node (ref "C17") (pin "1") (pinfunction "1_1") (pintype "passive"))
      (node (ref "GEN4") (pin "3") (pinfunction "CAP/2.5V_3") (pintype "bidirectional"))
    )
    (net (code "48") (name "Net-(GEN4-COMP)") (class "Default")
      (node (ref "C20") (pin "1") (pinfunction "1_1") (pintype "passive"))
      (node (ref "GEN4") (pin "1") (pinfunction "COMP_1") (pintype "bidirectional"))
    )
    (net (code "49") (name "Net-(GEN5-CAP{slash}2.5V)") (class "Default")
      (node (ref "C22") (pin "1") (pinfunction "1_1") (pintype "passive"))
      (node (ref "GEN5") (pin "3") (pinfunction "CAP/2.5V_3") (pintype "bidirectional"))
    )
    (net (code "50") (name "Net-(GEN5-COMP)") (class "Default")
      (node (ref "C24") (pin "1") (pinfunction "1_1") (pintype "passive"))
      (node (ref "GEN5") (pin "1") (pinfunction "COMP_1") (pintype "bidirectional"))
    )
    (net (code "51") (name "Net-(GEN6-CAP{slash}2.5V)") (class "Default")
      (node (ref "C26") (pin "1") (pinfunction "1_1") (pintype "passive"))
      (node (ref "GEN6") (pin "3") (pinfunction "CAP/2.5V_3") (pintype "bidirectional"))
    )
    (net (code "52") (name "Net-(GEN6-COMP)") (class "Default")
      (node (ref "C28") (pin "1") (pinfunction "1_1") (pintype "passive"))
      (node (ref "GEN6") (pin "1") (pinfunction "COMP_1") (pintype "bidirectional"))
    )
    (net (code "53") (name "Net-(GEN7-CAP{slash}2.5V)") (class "Default")
      (node (ref "C30") (pin "1") (pinfunction "1_1") (pintype "passive"))
      (node (ref "GEN7") (pin "3") (pinfunction "CAP/2.5V_3") (pintype "bidirectional"))
    )
    (net (code "54") (name "Net-(GEN7-COMP)") (class "Default")
      (node (ref "C32") (pin "1") (pinfunction "1_1") (pintype "passive"))
      (node (ref "GEN7") (pin "1") (pinfunction "COMP_1") (pintype "bidirectional"))
    )
    (net (code "55") (name "Net-(GEN8-CAP{slash}2.5V)") (class "Default")
      (node (ref "C34") (pin "1") (pinfunction "1_1") (pintype "passive"))
      (node (ref "GEN8") (pin "3") (pinfunction "CAP/2.5V_3") (pintype "bidirectional"))
    )
    (net (code "56") (name "Net-(GEN8-COMP)") (class "Default")
      (node (ref "C36") (pin "1") (pinfunction "1_1") (pintype "passive"))
      (node (ref "GEN8") (pin "1") (pinfunction "COMP_1") (pintype "bidirectional"))
    )
    (net (code "57") (name "Net-(GEN9-CAP{slash}2.5V)") (class "Default")
      (node (ref "C38") (pin "1") (pinfunction "1_1") (pintype "passive"))
      (node (ref "GEN9") (pin "3") (pinfunction "CAP/2.5V_3") (pintype "bidirectional"))
    )
    (net (code "58") (name "Net-(GEN9-COMP)") (class "Default")
      (node (ref "C40") (pin "1") (pinfunction "1_1") (pintype "passive"))
      (node (ref "GEN9") (pin "1") (pinfunction "COMP_1") (pintype "bidirectional"))
    )
    (net (code "59") (name "Net-(GEN10-CAP{slash}2.5V)") (class "Default")
      (node (ref "C42") (pin "1") (pinfunction "1_1") (pintype "passive"))
      (node (ref "GEN10") (pin "3") (pinfunction "CAP/2.5V_3") (pintype "bidirectional"))
    )
    (net (code "60") (name "Net-(GEN10-COMP)") (class "Default")
      (node (ref "C44") (pin "1") (pinfunction "1_1") (pintype "passive"))
      (node (ref "GEN10") (pin "1") (pinfunction "COMP_1") (pintype "bidirectional"))
    )
    (net (code "61") (name "Net-(GEN11-CAP{slash}2.5V)") (class "Default")
      (node (ref "C46") (pin "1") (pinfunction "1_1") (pintype "passive"))
      (node (ref "GEN11") (pin "3") (pinfunction "CAP/2.5V_3") (pintype "bidirectional"))
    )
    (net (code "62") (name "Net-(GEN11-COMP)") (class "Default")
      (node (ref "C48") (pin "1") (pinfunction "1_1") (pintype "passive"))
      (node (ref "GEN11") (pin "1") (pinfunction "COMP_1") (pintype "bidirectional"))
    )
    (net (code "63") (name "Net-(GEN12-CAP{slash}2.5V)") (class "Default")
      (node (ref "C50") (pin "1") (pinfunction "1_1") (pintype "passive"))
      (node (ref "GEN12") (pin "3") (pinfunction "CAP/2.5V_3") (pintype "bidirectional"))
    )
    (net (code "64") (name "Net-(GEN12-COMP)") (class "Default")
      (node (ref "C52") (pin "1") (pinfunction "1_1") (pintype "passive"))
      (node (ref "GEN12") (pin "1") (pinfunction "COMP_1") (pintype "bidirectional"))
    )
    (net (code "65") (name "Net-(GEN13-CAP{slash}2.5V)") (class "Default")
      (node (ref "C54") (pin "1") (pinfunction "1_1") (pintype "passive"))
      (node (ref "GEN13") (pin "3") (pinfunction "CAP/2.5V_3") (pintype "bidirectional"))
    )
    (net (code "66") (name "Net-(GEN13-COMP)") (class "Default")
      (node (ref "C56") (pin "1") (pinfunction "1_1") (pintype "passive"))
      (node (ref "GEN13") (pin "1") (pinfunction "COMP_1") (pintype "bidirectional"))
    )
    (net (code "67") (name "Net-(GEN14-CAP{slash}2.5V)") (class "Default")
      (node (ref "C58") (pin "1") (pinfunction "1_1") (pintype "passive"))
      (node (ref "GEN14") (pin "3") (pinfunction "CAP/2.5V_3") (pintype "bidirectional"))
    )
    (net (code "68") (name "Net-(GEN14-COMP)") (class "Default")
      (node (ref "C60") (pin "1") (pinfunction "1_1") (pintype "passive"))
      (node (ref "GEN14") (pin "1") (pinfunction "COMP_1") (pintype "bidirectional"))
    )
    (net (code "69") (name "Net-(GEN15-CAP{slash}2.5V)") (class "Default")
      (node (ref "C62") (pin "1") (pinfunction "1_1") (pintype "passive"))
      (node (ref "GEN15") (pin "3") (pinfunction "CAP/2.5V_3") (pintype "bidirectional"))
    )
    (net (code "70") (name "Net-(GEN15-COMP)") (class "Default")
      (node (ref "C64") (pin "1") (pinfunction "1_1") (pintype "passive"))
      (node (ref "GEN15") (pin "1") (pinfunction "COMP_1") (pintype "bidirectional"))
    )
    (net (code "71") (name "Net-(GEN16-CAP{slash}2.5V)") (class "Default")
      (node (ref "C66") (pin "1") (pinfunction "1_1") (pintype "passive"))
      (node (ref "GEN16") (pin "3") (pinfunction "CAP/2.5V_3") (pintype "bidirectional"))
    )
    (net (code "72") (name "Net-(GEN16-COMP)") (class "Default")
      (node (ref "C68") (pin "1") (pinfunction "1_1") (pintype "passive"))
      (node (ref "GEN16") (pin "1") (pinfunction "COMP_1") (pintype "bidirectional"))
    )
    (net (code "73") (name "Net-(IC2-(RXD)PD0)") (class "Default")
      (node (ref "IC2") (pin "14") (pinfunction "(RXD)PD0_14") (pintype "bidirectional"))
      (node (ref "JP2") (pin "3") (pinfunction "3_3") (pintype "passive"))
    )
    (net (code "74") (name "Net-(IC2-(TXD)PD1)") (class "Default")
      (node (ref "IC2") (pin "15") (pinfunction "(TXD)PD1_15") (pintype "bidirectional"))
      (node (ref "JP2") (pin "2") (pinfunction "2_2") (pintype "passive"))
    )
    (net (code "75") (name "Net-(IC2-XTAL1)") (class "Default")
      (node (ref "C2") (pin "2") (pinfunction "2_2") (pintype "passive"))
      (node (ref "IC2") (pin "13") (pinfunction "XTAL1_13") (pintype "bidirectional"))
      (node (ref "Q1") (pin "1") (pinfunction "1_1") (pintype "passive"))
    )
    (net (code "76") (name "Net-(IC2-XTAL2)") (class "Default")
      (node (ref "C1") (pin "2") (pinfunction "2_2") (pintype "passive"))
      (node (ref "IC2") (pin "12") (pinfunction "XTAL2_12") (pintype "bidirectional"))
      (node (ref "Q1") (pin "2") (pinfunction "2_2") (pintype "passive"))
    )
    (net (code "77") (name "VCC") (class "Default")
      (node (ref "C10") (pin "2") (pinfunction "2_2") (pintype "passive"))
      (node (ref "C12") (pin "+") (pinfunction "+_+") (pintype "passive"))
      (node (ref "C13") (pin "2") (pinfunction "2_2") (pintype "passive"))
      (node (ref "C14") (pin "2") (pinfunction "2_2") (pintype "passive"))
      (node (ref "C15") (pin "1") (pinfunction "1_1") (pintype "passive"))
      (node (ref "C16") (pin "1") (pinfunction "1_1") (pintype "passive"))
      (node (ref "C18") (pin "+") (pinfunction "+_+") (pintype "passive"))
      (node (ref "C19") (pin "+") (pinfunction "+_+") (pintype "passive"))
      (node (ref "C20") (pin "2") (pinfunction "2_2") (pintype "passive"))
      (node (ref "C21") (pin "2") (pinfunction "2_2") (pintype "passive"))
      (node (ref "C23") (pin "+") (pinfunction "+_+") (pintype "passive"))
      (node (ref "C24") (pin "2") (pinfunction "2_2") (pintype "passive"))
      (node (ref "C25") (pin "2") (pinfunction "2_2") (pintype "passive"))
      (node (ref "C27") (pin "+") (pinfunction "+_+") (pintype "passive"))
      (node (ref "C28") (pin "2") (pinfunction "2_2") (pintype "passive"))
      (node (ref "C29") (pin "2") (pinfunction "2_2") (pintype "passive"))
      (node (ref "C3") (pin "2") (pinfunction "2_2") (pintype "passive"))
      (node (ref "C31") (pin "+") (pinfunction "+_+") (pintype "passive"))
      (node (ref "C32") (pin "2") (pinfunction "2_2") (pintype "passive"))
      (node (ref "C33") (pin "2") (pinfunction "2_2") (pintype "passive"))
      (node (ref "C35") (pin "+") (pinfunction "+_+") (pintype "passive"))
      (node (ref "C36") (pin "2") (pinfunction "2_2") (pintype "passive"))
      (node (ref "C37") (pin "2") (pinfunction "2_2") (pintype "passive"))
      (node (ref "C39") (pin "+") (pinfunction "+_+") (pintype "passive"))
      (node (ref "C4") (pin "2") (pinfunction "2_2") (pintype "passive"))
      (node (ref "C40") (pin "2") (pinfunction "2_2") (pintype "passive"))
      (node (ref "C41") (pin "2") (pinfunction "2_2") (pintype "passive"))
      (node (ref "C43") (pin "+") (pinfunction "+_+") (pintype "passive"))
      (node (ref "C44") (pin "2") (pinfunction "2_2") (pintype "passive"))
      (node (ref "C45") (pin "2") (pinfunction "2_2") (pintype "passive"))
      (node (ref "C47") (pin "+") (pinfunction "+_+") (pintype "passive"))
      (node (ref "C48") (pin "2") (pinfunction "2_2") (pintype "passive"))
      (node (ref "C49") (pin "2") (pinfunction "2_2") (pintype "passive"))
      (node (ref "C51") (pin "+") (pinfunction "+_+") (pintype "passive"))
      (node (ref "C52") (pin "2") (pinfunction "2_2") (pintype "passive"))
      (node (ref "C53") (pin "2") (pinfunction "2_2") (pintype "passive"))
      (node (ref "C55") (pin "+") (pinfunction "+_+") (pintype "passive"))
      (node (ref "C56") (pin "2") (pinfunction "2_2") (pintype "passive"))
      (node (ref "C57") (pin "2") (pinfunction "2_2") (pintype "passive"))
      (node (ref "C59") (pin "+") (pinfunction "+_+") (pintype "passive"))
      (node (ref "C6") (pin "2") (pinfunction "2_2") (pintype "passive"))
      (node (ref "C60") (pin "2") (pinfunction "2_2") (pintype "passive"))
      (node (ref "C61") (pin "2") (pinfunction "2_2") (pintype "passive"))
      (node (ref "C63") (pin "+") (pinfunction "+_+") (pintype "passive"))
      (node (ref "C64") (pin "2") (pinfunction "2_2") (pintype "passive"))
      (node (ref "C65") (pin "2") (pinfunction "2_2") (pintype "passive"))
      (node (ref "C67") (pin "+") (pinfunction "+_+") (pintype "passive"))
      (node (ref "C68") (pin "2") (pinfunction "2_2") (pintype "passive"))
      (node (ref "C8") (pin "+") (pinfunction "+_+") (pintype "passive"))
      (node (ref "C9") (pin "2") (pinfunction "2_2") (pintype "passive"))
      (node (ref "GEN1") (pin "2") (pinfunction "VDD_2") (pintype "bidirectional"))
      (node (ref "GEN10") (pin "2") (pinfunction "VDD_2") (pintype "bidirectional"))
      (node (ref "GEN11") (pin "2") (pinfunction "VDD_2") (pintype "bidirectional"))
      (node (ref "GEN12") (pin "2") (pinfunction "VDD_2") (pintype "bidirectional"))
      (node (ref "GEN13") (pin "2") (pinfunction "VDD_2") (pintype "bidirectional"))
      (node (ref "GEN14") (pin "2") (pinfunction "VDD_2") (pintype "bidirectional"))
      (node (ref "GEN15") (pin "2") (pinfunction "VDD_2") (pintype "bidirectional"))
      (node (ref "GEN16") (pin "2") (pinfunction "VDD_2") (pintype "bidirectional"))
      (node (ref "GEN2") (pin "2") (pinfunction "VDD_2") (pintype "bidirectional"))
      (node (ref "GEN3") (pin "2") (pinfunction "VDD_2") (pintype "bidirectional"))
      (node (ref "GEN4") (pin "2") (pinfunction "VDD_2") (pintype "bidirectional"))
      (node (ref "GEN5") (pin "2") (pinfunction "VDD_2") (pintype "bidirectional"))
      (node (ref "GEN6") (pin "2") (pinfunction "VDD_2") (pintype "bidirectional"))
      (node (ref "GEN7") (pin "2") (pinfunction "VDD_2") (pintype "bidirectional"))
      (node (ref "GEN8") (pin "2") (pinfunction "VDD_2") (pintype "bidirectional"))
      (node (ref "GEN9") (pin "2") (pinfunction "VDD_2") (pintype "bidirectional"))
      (node (ref "IC2") (pin "10") (pinfunction "VCC_10") (pintype "power_in"))
      (node (ref "IC2") (pin "30") (pinfunction "AVCC_30") (pintype "power_in"))
      (node (ref "JP1") (pin "2") (pinfunction "2_2") (pintype "passive"))
      (node (ref "JP2") (pin "4") (pinfunction "4_4") (pintype "passive"))
      (node (ref "JP3") (pin "2") (pinfunction "2_2") (pintype "passive"))
      (node (ref "R1") (pin "1") (pinfunction "1_1") (pintype "passive"))
      (node (ref "R2") (pin "2") (pinfunction "2_2") (pintype "passive"))
      (node (ref "R3") (pin "2") (pinfunction "2_2") (pintype "passive"))
    )
    (net (code "78") (name "unconnected-(IC2-(ICP)PD6-Pad20)") (class "Default")
      (node (ref "IC2") (pin "20") (pinfunction "(ICP)PD6_20") (pintype "bidirectional"))
    )
    (net (code "79") (name "unconnected-(IC2-(INT0)PD2-Pad16)") (class "Default")
      (node (ref "IC2") (pin "16") (pinfunction "(INT0)PD2_16") (pintype "bidirectional"))
    )
    (net (code "80") (name "unconnected-(IC2-(INT1)PD3-Pad17)") (class "Default")
      (node (ref "IC2") (pin "17") (pinfunction "(INT1)PD3_17") (pintype "bidirectional"))
    )
    (net (code "81") (name "unconnected-(IC2-(OC1A)PD5-Pad19)") (class "Default")
      (node (ref "IC2") (pin "19") (pinfunction "(OC1A)PD5_19") (pintype "bidirectional"))
    )
    (net (code "82") (name "unconnected-(IC2-(OC1B)PD4-Pad18)") (class "Default")
      (node (ref "IC2") (pin "18") (pinfunction "(OC1B)PD4_18") (pintype "bidirectional"))
    )
    (net (code "83") (name "unconnected-(IC2-(OC2)PD7-Pad21)") (class "Default")
      (node (ref "IC2") (pin "21") (pinfunction "(OC2)PD7_21") (pintype "bidirectional"))
    )
    (net (code "84") (name "unconnected-(IC2-(SS)PB4-Pad5)") (class "Default")
      (node (ref "IC2") (pin "5") (pinfunction "(SS)PB4_5") (pintype "bidirectional"))
    )
    (net (code "85") (name "unconnected-(IC2-(T1)PB1-Pad2)") (class "Default")
      (node (ref "IC2") (pin "2") (pinfunction "(T1)PB1_2") (pintype "bidirectional"))
    )
    (net (code "86") (name "unconnected-(IC2-AREF-Pad32)") (class "Default")
      (node (ref "IC2") (pin "32") (pinfunction "AREF_32") (pintype "passive"))
    )
    (net (code "87") (name "unconnected-(JP2-Pad1)") (class "Default")
      (node (ref "JP2") (pin "1") (pinfunction "1_1") (pintype "passive"))
    )
    (net (code "88") (name "unconnected-(JP2-Pad5)") (class "Default")
      (node (ref "JP2") (pin "5") (pinfunction "5_5") (pintype "passive"))
    )
  )
)
